# power.net
KiCad netlist of a schematic drawn in Altium Designer
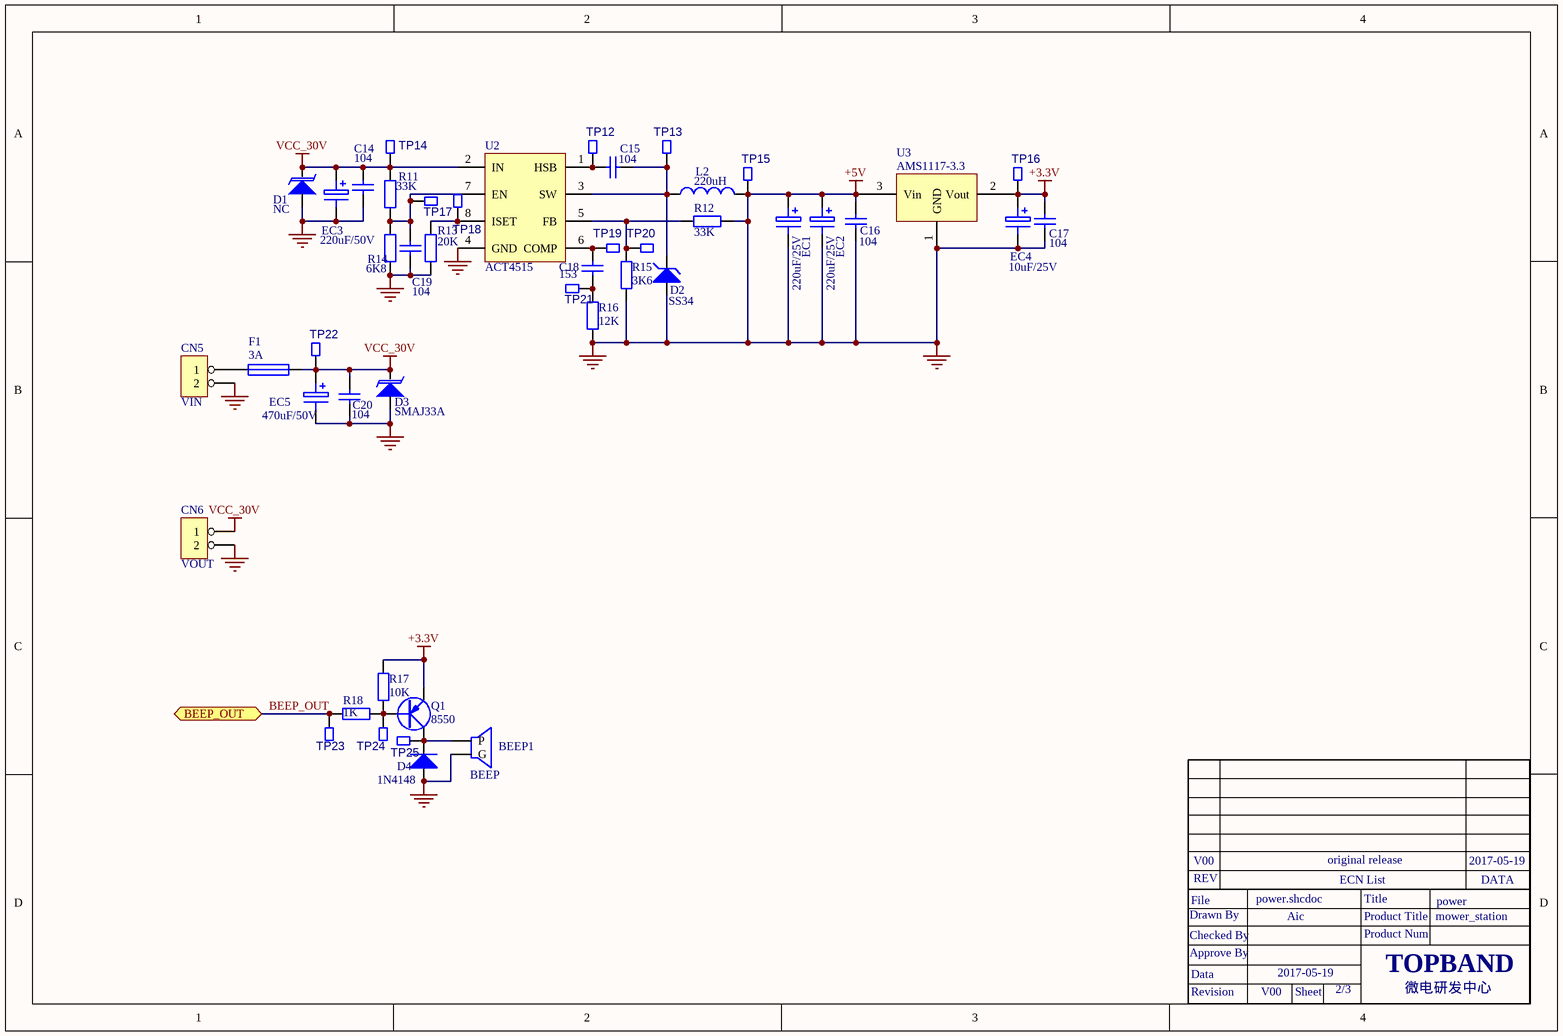
[diagram p0: power.SchDoc]

(export (version "E")
  (design (tool "Eeschema 10.0.6"))
  (components
    (comp (ref "BEEP1") (value "BEEP") (footprint "BELL-5") (libsource (lib "STM32F429_F746") (part "BEEP")))
    (comp (ref "C14")
      (value "104")
      (footprint "0603C")
      (libsource (lib "altium-import") (part "root_1_mirrored_Cap(0603)_"))
    )
    (comp (ref "C15")
      (value "104")
      (footprint "0603C")
      (libsource (lib "altium-import") (part "root_2_mirrored_Cap(0603)_"))
    )
    (comp (ref "C16")
      (value "104")
      (footprint "0603C")
      (libsource (lib "altium-import") (part "root_1_mirrored_Cap(0603)_"))
    )
    (comp (ref "C17")
      (value "104")
      (footprint "0603C")
      (libsource (lib "altium-import") (part "root_1_mirrored_Cap(0603)_"))
    )
    (comp (ref "C18")
      (value "153")
      (footprint "0603C")
      (libsource (lib "altium-import") (part "root_1_mirrored_Cap(0603)_"))
    )
    (comp (ref "C19")
      (value "104")
      (footprint "0603C")
      (libsource (lib "altium-import") (part "root_1_mirrored_Cap(0603)_"))
    )
    (comp (ref "C20")
      (value "104")
      (footprint "0805C")
      (libsource (lib "altium-import") (part "root_3_mirrored_Cap(0603)_"))
    )
    (comp (ref "CN5")
      (value "VIN")
      (footprint "CON2-2.54")
      (description "插座")
      (fields (field (name "PART NUMBER") "2Pin(卧式)"))
      (libsource (lib "接插器件+IC") (part "2Pin(卧式)"))
    )
    (comp (ref "CN6")
      (value "VOUT")
      (footprint "CON2-2.54")
      (description "插座")
      (fields (field (name "PART NUMBER") "2Pin(卧式)"))
      (libsource (lib "接插器件+IC") (part "2Pin(卧式)"))
    )
    (comp (ref "D1")
      (value "NC")
      (footprint "SOD-123")
      (description "TVS管")
      (fields (field (name "PART NUMBER") "Diode(TVS_贴片)_1"))
      (libsource (lib "分立器件1") (part "Diode(TVS_贴片)_1"))
    )
    (comp (ref "D2")
      (value "SS34")
      (footprint "SMA")
      (description "稳压二极管")
      (fields (field (name "PART NUMBER") "D Zener(贴片)"))
      (libsource (lib "分立器件1") (part "D Zener(贴片)"))
    )
    (comp (ref "D3")
      (value "SMAJ33A")
      (footprint "DO-214AC")
      (description "TVS管")
      (fields (field (name "PART NUMBER") "Diode(TVS_贴片)_1"))
      (libsource (lib "分立器件1") (part "Diode(TVS_贴片)_1"))
    )
    (comp (ref "D4")
      (value "1N4148")
      (footprint "SOD-123")
      (description "二极管")
      (fields (field (name "PART NUMBER") "Diode(DO-35)-D"))
      (libsource (lib "分立器件1") (part "Diode(DO-35)-D"))
    )
    (comp (ref "EC1")
      (value "220uF/25V")
      (footprint "EC10")
      (description "电解电容")
      (fields (field (name "PART NUMBER") "Electro(2.5mm)"))
      (libsource (lib "分立器件1") (part "Electro(2.5mm)"))
    )
    (comp (ref "EC2")
      (value "220uF/25V")
      (footprint "EC10")
      (description "电解电容")
      (fields (field (name "PART NUMBER") "Electro(2.5mm)"))
      (libsource (lib "分立器件1") (part "Electro(2.5mm)"))
    )
    (comp (ref "EC3")
      (value "220uF/50V")
      (footprint "EC10")
      (description "电解电容")
      (fields (field (name "PART NUMBER") "Electro(2.5mm)"))
      (libsource (lib "分立器件1") (part "Electro(2.5mm)"))
    )
    (comp (ref "EC4")
      (value "10uF/25V")
      (footprint "EC4")
      (description "电解电容")
      (fields (field (name "PART NUMBER") "Electro(2.5mm)"))
      (libsource (lib "分立器件1") (part "Electro(2.5mm)"))
    )
    (comp (ref "EC5")
      (value "470uF/50V")
      (footprint "EC12.5")
      (description "电解电容")
      (fields (field (name "PART NUMBER") "Electro(2.5mm)"))
      (libsource (lib "分立器件1") (part "Electro(2.5mm)"))
    )
    (comp (ref "F1")
      (value "3A")
      (footprint "0603")
      (description "保险管")
      (fields (field (name "PART NUMBER") "Fuse(1206)"))
      (libsource (lib "分立器件1") (part "Fuse(1206)"))
    )
    (comp (ref "L2")
      (value "220uH")
      (footprint "150700618")
      (description "电感")
      (fields (field (name "PART NUMBER") "Inductor(0805)"))
      (libsource (lib "分立器件1") (part "Inductor(0805)"))
    )
    (comp (ref "Q1")
      (value "8550")
      (footprint "SOT-23-BCE")
      (description "三极管")
      (fields (field (name "PART NUMBER") "PNP(贴片)"))
      (libsource (lib "分立器件1") (part "PNP(贴片)"))
    )
    (comp (ref "R11")
      (value "33K")
      (footprint "0603R")
      (description "Resistor")
      (fields (field (name "PUBLISHER") "Altium Limited"))
      (libsource (lib "Miscellaneous Devices") (part "Res2"))
    )
    (comp (ref "R12")
      (value "33K")
      (footprint "0603R")
      (description "Resistor")
      (fields (field (name "PUBLISHER") "Altium Limited"))
      (libsource (lib "") (part "Res2_1"))
    )
    (comp (ref "R13")
      (value "20K")
      (footprint "0603R")
      (description "Resistor")
      (fields (field (name "PUBLISHER") "Altium Limited"))
      (libsource (lib "Miscellaneous Devices") (part "Res2"))
    )
    (comp (ref "R14")
      (value "6K8")
      (footprint "0603R")
      (description "Resistor")
      (fields (field (name "PUBLISHER") "Altium Limited"))
      (libsource (lib "Miscellaneous Devices") (part "Res2"))
    )
    (comp (ref "R15")
      (value "3K6")
      (footprint "0603R")
      (description "Resistor")
      (fields (field (name "PUBLISHER") "Altium Limited"))
      (libsource (lib "") (part "Res2_2"))
    )
    (comp (ref "R16")
      (value "12K")
      (footprint "0603R")
      (description "Resistor")
      (fields (field (name "PUBLISHER") "Altium Limited"))
      (libsource (lib "") (part "Res2_2"))
    )
    (comp (ref "R17")
      (value "10K")
      (footprint "0603R")
      (description "电阻器")
      (fields (field (name "PART NUMBER") "Res(0603)"))
      (libsource (lib "") (part "Res(0603)_1"))
    )
    (comp (ref "R18")
      (value "1K")
      (footprint "0603R")
      (description "电阻器")
      (fields (field (name "PART NUMBER") "Res(0603)"))
      (libsource (lib "分立器件1") (part "Res(0603)"))
    )
    (comp (ref "TP12") (value "TP") (footprint "TEST-0.8MM") (libsource (lib "Topband1") (part "TP")))
    (comp (ref "TP13") (value "TP") (footprint "TEST-0.8MM") (libsource (lib "Topband1") (part "TP")))
    (comp (ref "TP14") (value "TP") (footprint "TEST-0.8MM") (libsource (lib "Topband1") (part "TP")))
    (comp (ref "TP15") (value "TP") (footprint "TEST-0.8MM") (libsource (lib "Topband1") (part "TP")))
    (comp (ref "TP16") (value "TP") (footprint "TEST-0.8MM") (libsource (lib "Topband1") (part "TP")))
    (comp (ref "TP17") (value "TP") (footprint "TEST-0.8MM") (libsource (lib "Topband1") (part "TP")))
    (comp (ref "TP18") (value "TP") (footprint "TEST-0.8MM") (libsource (lib "Topband1") (part "TP")))
    (comp (ref "TP19") (value "TP") (footprint "TEST-0.8MM") (libsource (lib "Topband1") (part "TP")))
    (comp (ref "TP20") (value "TP") (footprint "TEST-0.8MM") (libsource (lib "Topband1") (part "TP")))
    (comp (ref "TP21") (value "TP") (footprint "TEST-0.8MM") (libsource (lib "Topband1") (part "TP")))
    (comp (ref "TP22") (value "TP") (footprint "TEST-0.8MM") (libsource (lib "Topband1") (part "TP")))
    (comp (ref "TP23") (value "TP") (footprint "TEST-0.8MM") (libsource (lib "Topband1") (part "TP")))
    (comp (ref "TP24") (value "TP") (footprint "TEST-0.8MM") (libsource (lib "Topband1") (part "TP")))
    (comp (ref "TP25") (value "TP") (footprint "TEST-0.8MM") (libsource (lib "Topband1") (part "TP")))
    (comp (ref "U2") (value "ACT4515") (footprint "SOP-8") (libsource (lib "Schlib1") (part "ACT4515")))
    (comp (ref "U3") (value "AMS1117-3.3") (footprint "SOT-223") (libsource (lib "IC") (part "AMS1117-3.3")))
  )
  (nets
    (net (code "1") (name "+3.3V") (class "Default")
      (node (ref "C17") (pin "1") (pinfunction "1_1") (pintype "passive"))
      (node (ref "EC4") (pin "1") (pinfunction "1_1") (pintype "passive"))
      (node (ref "Q1") (pin "E") (pinfunction "E_E") (pintype "passive"))
      (node (ref "R17") (pin "2") (pinfunction "2_2") (pintype "passive"))
      (node (ref "TP16") (pin "1") (pintype "passive"))
      (node (ref "U3") (pin "2") (pinfunction "Vout_2") (pintype "passive"))
    )
    (net (code "2") (name "+5V") (class "Default")
      (node (ref "BEEP1") (pin "2") (pinfunction "G_2") (pintype "passive"))
      (node (ref "C14") (pin "2") (pinfunction "2_2") (pintype "passive"))
      (node (ref "C16") (pin "1") (pinfunction "1_1") (pintype "passive"))
      (node (ref "C16") (pin "2") (pinfunction "2_2") (pintype "passive"))
      (node (ref "C17") (pin "2") (pinfunction "2_2") (pintype "passive"))
      (node (ref "C19") (pin "2") (pinfunction "2_2") (pintype "passive"))
      (node (ref "C20") (pin "1") (pinfunction "1_1") (pintype "passive"))
      (node (ref "CN5") (pin "2") (pinfunction "2_2") (pintype "passive"))
      (node (ref "CN6") (pin "2") (pinfunction "2_2") (pintype "passive"))
      (node (ref "D1") (pin "A") (pinfunction "A_A") (pintype "passive"))
      (node (ref "D2") (pin "A") (pinfunction "A_A") (pintype "passive"))
      (node (ref "D3") (pin "A") (pinfunction "A_A") (pintype "passive"))
      (node (ref "D4") (pin "A") (pinfunction "A_A") (pintype "passive"))
      (node (ref "EC1") (pin "1") (pinfunction "1_1") (pintype "passive"))
      (node (ref "EC1") (pin "2") (pinfunction "2_2") (pintype "passive"))
      (node (ref "EC2") (pin "1") (pinfunction "1_1") (pintype "passive"))
      (node (ref "EC2") (pin "2") (pinfunction "2_2") (pintype "passive"))
      (node (ref "EC3") (pin "2") (pinfunction "2_2") (pintype "passive"))
      (node (ref "EC4") (pin "2") (pinfunction "2_2") (pintype "passive"))
      (node (ref "EC5") (pin "2") (pinfunction "2_2") (pintype "passive"))
      (node (ref "L2") (pin "2") (pinfunction "2_2") (pintype "passive"))
      (node (ref "R12") (pin "1") (pinfunction "1_1") (pintype "passive"))
      (node (ref "R13") (pin "2") (pinfunction "2_2") (pintype "passive"))
      (node (ref "R14") (pin "2") (pinfunction "2_2") (pintype "passive"))
      (node (ref "R15") (pin "1") (pinfunction "1_1") (pintype "passive"))
      (node (ref "R16") (pin "1") (pinfunction "1_1") (pintype "passive"))
      (node (ref "TP15") (pin "1") (pintype "passive"))
      (node (ref "U2") (pin "4") (pinfunction "GND_4") (pintype "passive"))
      (node (ref "U3") (pin "1") (pinfunction "GND_1") (pintype "passive"))
      (node (ref "U3") (pin "3") (pinfunction "Vin_3") (pintype "passive"))
    )
    (net (code "3") (name "/BEEP_OUT") (class "Default")
      (node (ref "R18") (pin "1") (pinfunction "1_1") (pintype "passive"))
      (node (ref "TP23") (pin "1") (pintype "passive"))
    )
    (net (code "4") (name "Net-(BEEP1-P)") (class "Default")
      (node (ref "BEEP1") (pin "1") (pinfunction "P_1") (pintype "passive"))
      (node (ref "D4") (pin "K") (pinfunction "K_K") (pintype "passive"))
      (node (ref "Q1") (pin "C") (pinfunction "C_C") (pintype "passive"))
      (node (ref "TP25") (pin "1") (pintype "passive"))
    )
    (net (code "5") (name "Net-(C18-Pad2)") (class "Default")
      (node (ref "C18") (pin "2") (pinfunction "2_2") (pintype "passive"))
      (node (ref "R16") (pin "2") (pinfunction "2_2") (pintype "passive"))
      (node (ref "TP21") (pin "1") (pintype "passive"))
    )
    (net (code "6") (name "Net-(CN5-Pad1)") (class "Default")
      (node (ref "CN5") (pin "1") (pinfunction "1_1") (pintype "passive"))
      (node (ref "F1") (pin "1") (pinfunction "1_1") (pintype "passive"))
    )
    (net (code "7") (name "Net-(Q1-PadB)") (class "Default")
      (node (ref "Q1") (pin "B") (pinfunction "B_B") (pintype "passive"))
      (node (ref "R17") (pin "1") (pinfunction "1_1") (pintype "passive"))
      (node (ref "R18") (pin "2") (pinfunction "2_2") (pintype "passive"))
      (node (ref "TP24") (pin "1") (pintype "passive"))
    )
    (net (code "8") (name "Net-(U2-COMP)") (class "Default")
      (node (ref "C18") (pin "1") (pinfunction "1_1") (pintype "passive"))
      (node (ref "TP19") (pin "1") (pintype "passive"))
      (node (ref "U2") (pin "6") (pinfunction "COMP_6") (pintype "passive"))
    )
    (net (code "9") (name "Net-(U2-EN)") (class "Default")
      (node (ref "C19") (pin "1") (pinfunction "1_1") (pintype "passive"))
      (node (ref "R11") (pin "2") (pinfunction "2_2") (pintype "passive"))
      (node (ref "R14") (pin "1") (pinfunction "1_1") (pintype "passive"))
      (node (ref "TP17") (pin "1") (pintype "passive"))
      (node (ref "U2") (pin "7") (pinfunction "EN_7") (pintype "passive"))
    )
    (net (code "10") (name "Net-(U2-FB)") (class "Default")
      (node (ref "R12") (pin "2") (pinfunction "2_2") (pintype "passive"))
      (node (ref "R15") (pin "2") (pinfunction "2_2") (pintype "passive"))
      (node (ref "TP20") (pin "1") (pintype "passive"))
      (node (ref "U2") (pin "5") (pinfunction "FB_5") (pintype "passive"))
    )
    (net (code "11") (name "Net-(U2-HSB)") (class "Default")
      (node (ref "C15") (pin "1") (pinfunction "1_1") (pintype "passive"))
      (node (ref "TP12") (pin "1") (pintype "passive"))
      (node (ref "U2") (pin "1") (pinfunction "HSB_1") (pintype "passive"))
    )
    (net (code "12") (name "Net-(U2-ISET)") (class "Default")
      (node (ref "R13") (pin "1") (pinfunction "1_1") (pintype "passive"))
      (node (ref "TP18") (pin "1") (pintype "passive"))
      (node (ref "U2") (pin "8") (pinfunction "ISET_8") (pintype "passive"))
    )
    (net (code "13") (name "Net-(U2-SW)") (class "Default")
      (node (ref "C15") (pin "2") (pinfunction "2_2") (pintype "passive"))
      (node (ref "D2") (pin "K") (pinfunction "K_K") (pintype "passive"))
      (node (ref "L2") (pin "1") (pinfunction "1_1") (pintype "passive"))
      (node (ref "TP13") (pin "1") (pintype "passive"))
      (node (ref "U2") (pin "3") (pinfunction "SW_3") (pintype "passive"))
    )
    (net (code "14") (name "VCC_30V") (class "Default")
      (node (ref "C14") (pin "1") (pinfunction "1_1") (pintype "passive"))
      (node (ref "C20") (pin "2") (pinfunction "2_2") (pintype "passive"))
      (node (ref "CN6") (pin "1") (pinfunction "1_1") (pintype "passive"))
      (node (ref "D1") (pin "K") (pinfunction "K_K") (pintype "passive"))
      (node (ref "D3") (pin "K") (pinfunction "K_K") (pintype "passive"))
      (node (ref "EC3") (pin "1") (pinfunction "1_1") (pintype "passive"))
      (node (ref "EC5") (pin "1") (pinfunction "1_1") (pintype "passive"))
      (node (ref "F1") (pin "2") (pinfunction "2_2") (pintype "passive"))
      (node (ref "R11") (pin "1") (pinfunction "1_1") (pintype "passive"))
      (node (ref "TP14") (pin "1") (pintype "passive"))
      (node (ref "TP22") (pin "1") (pintype "passive"))
      (node (ref "U2") (pin "2") (pinfunction "IN_2") (pintype "passive"))
    )
  )
)
